# flap.net
KiCad netlist of a schematic drawn in Altium Designer
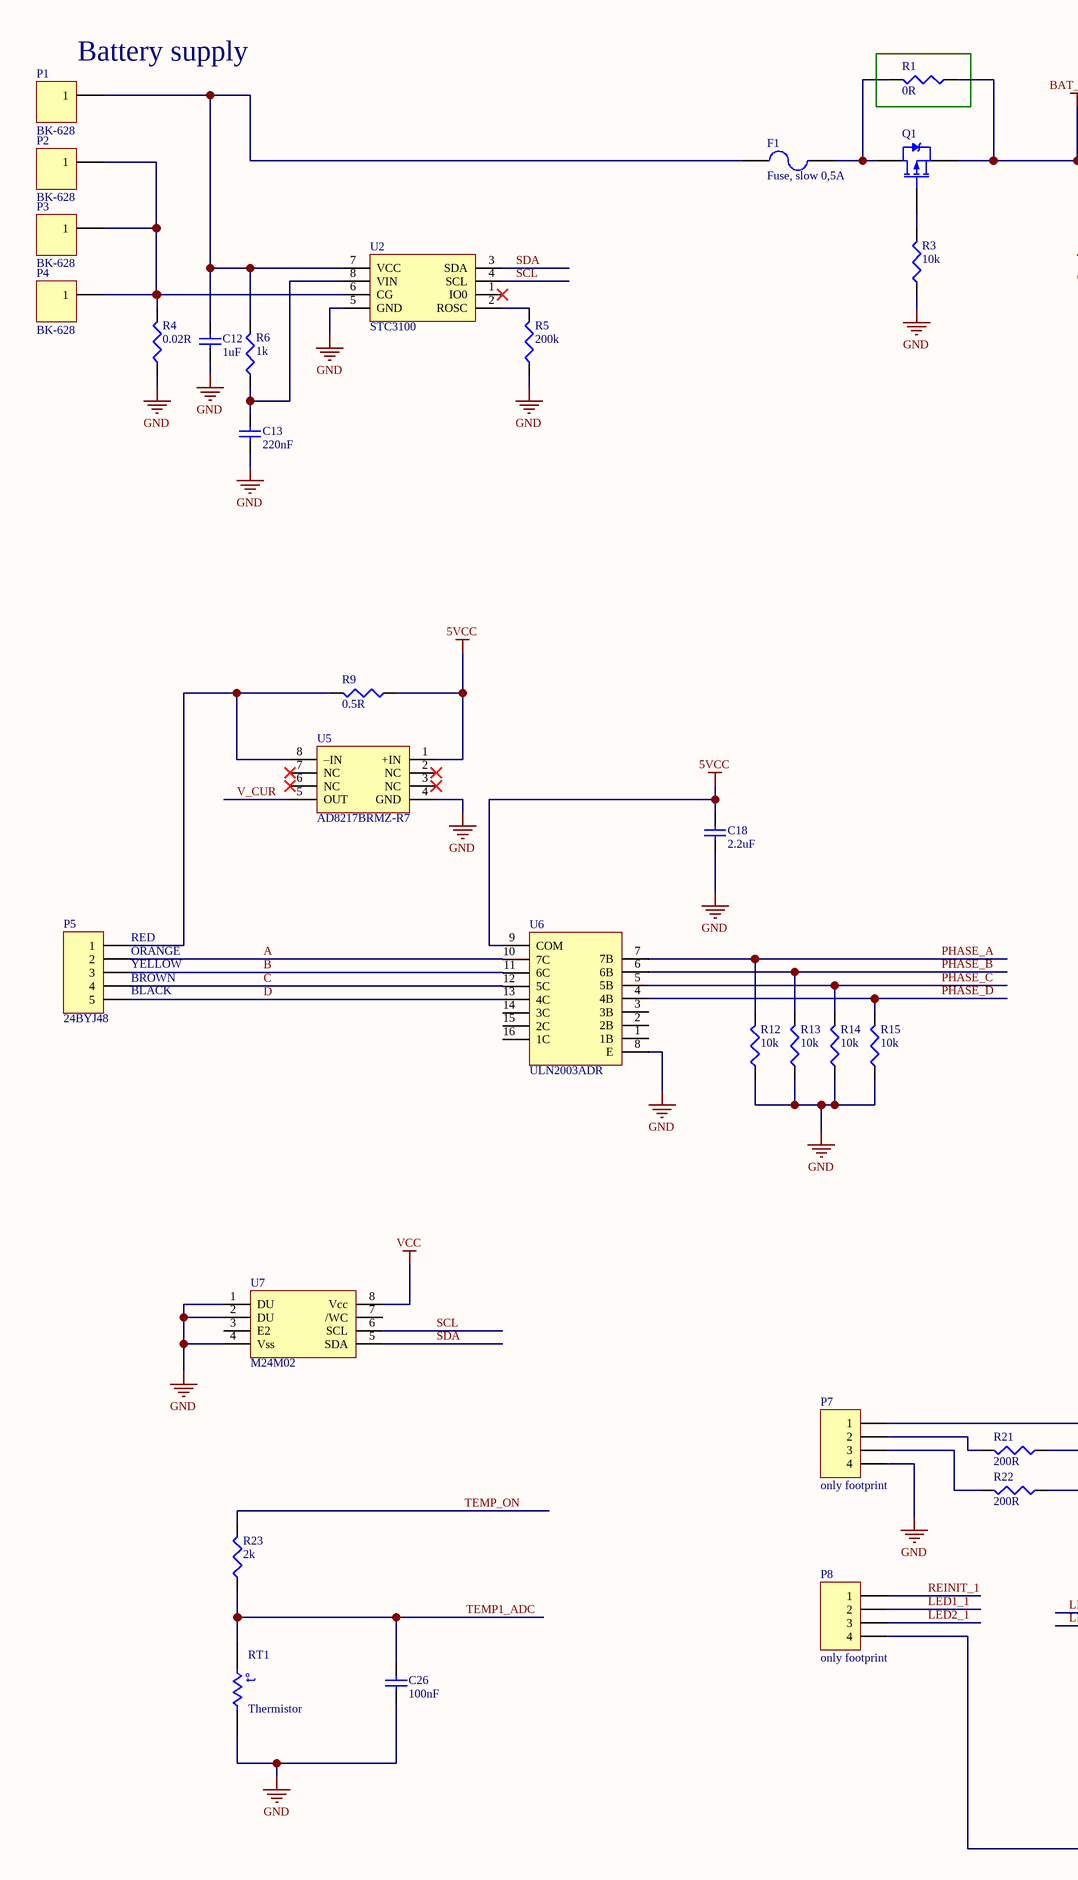
[diagram p0: flap.SchDoc, left]
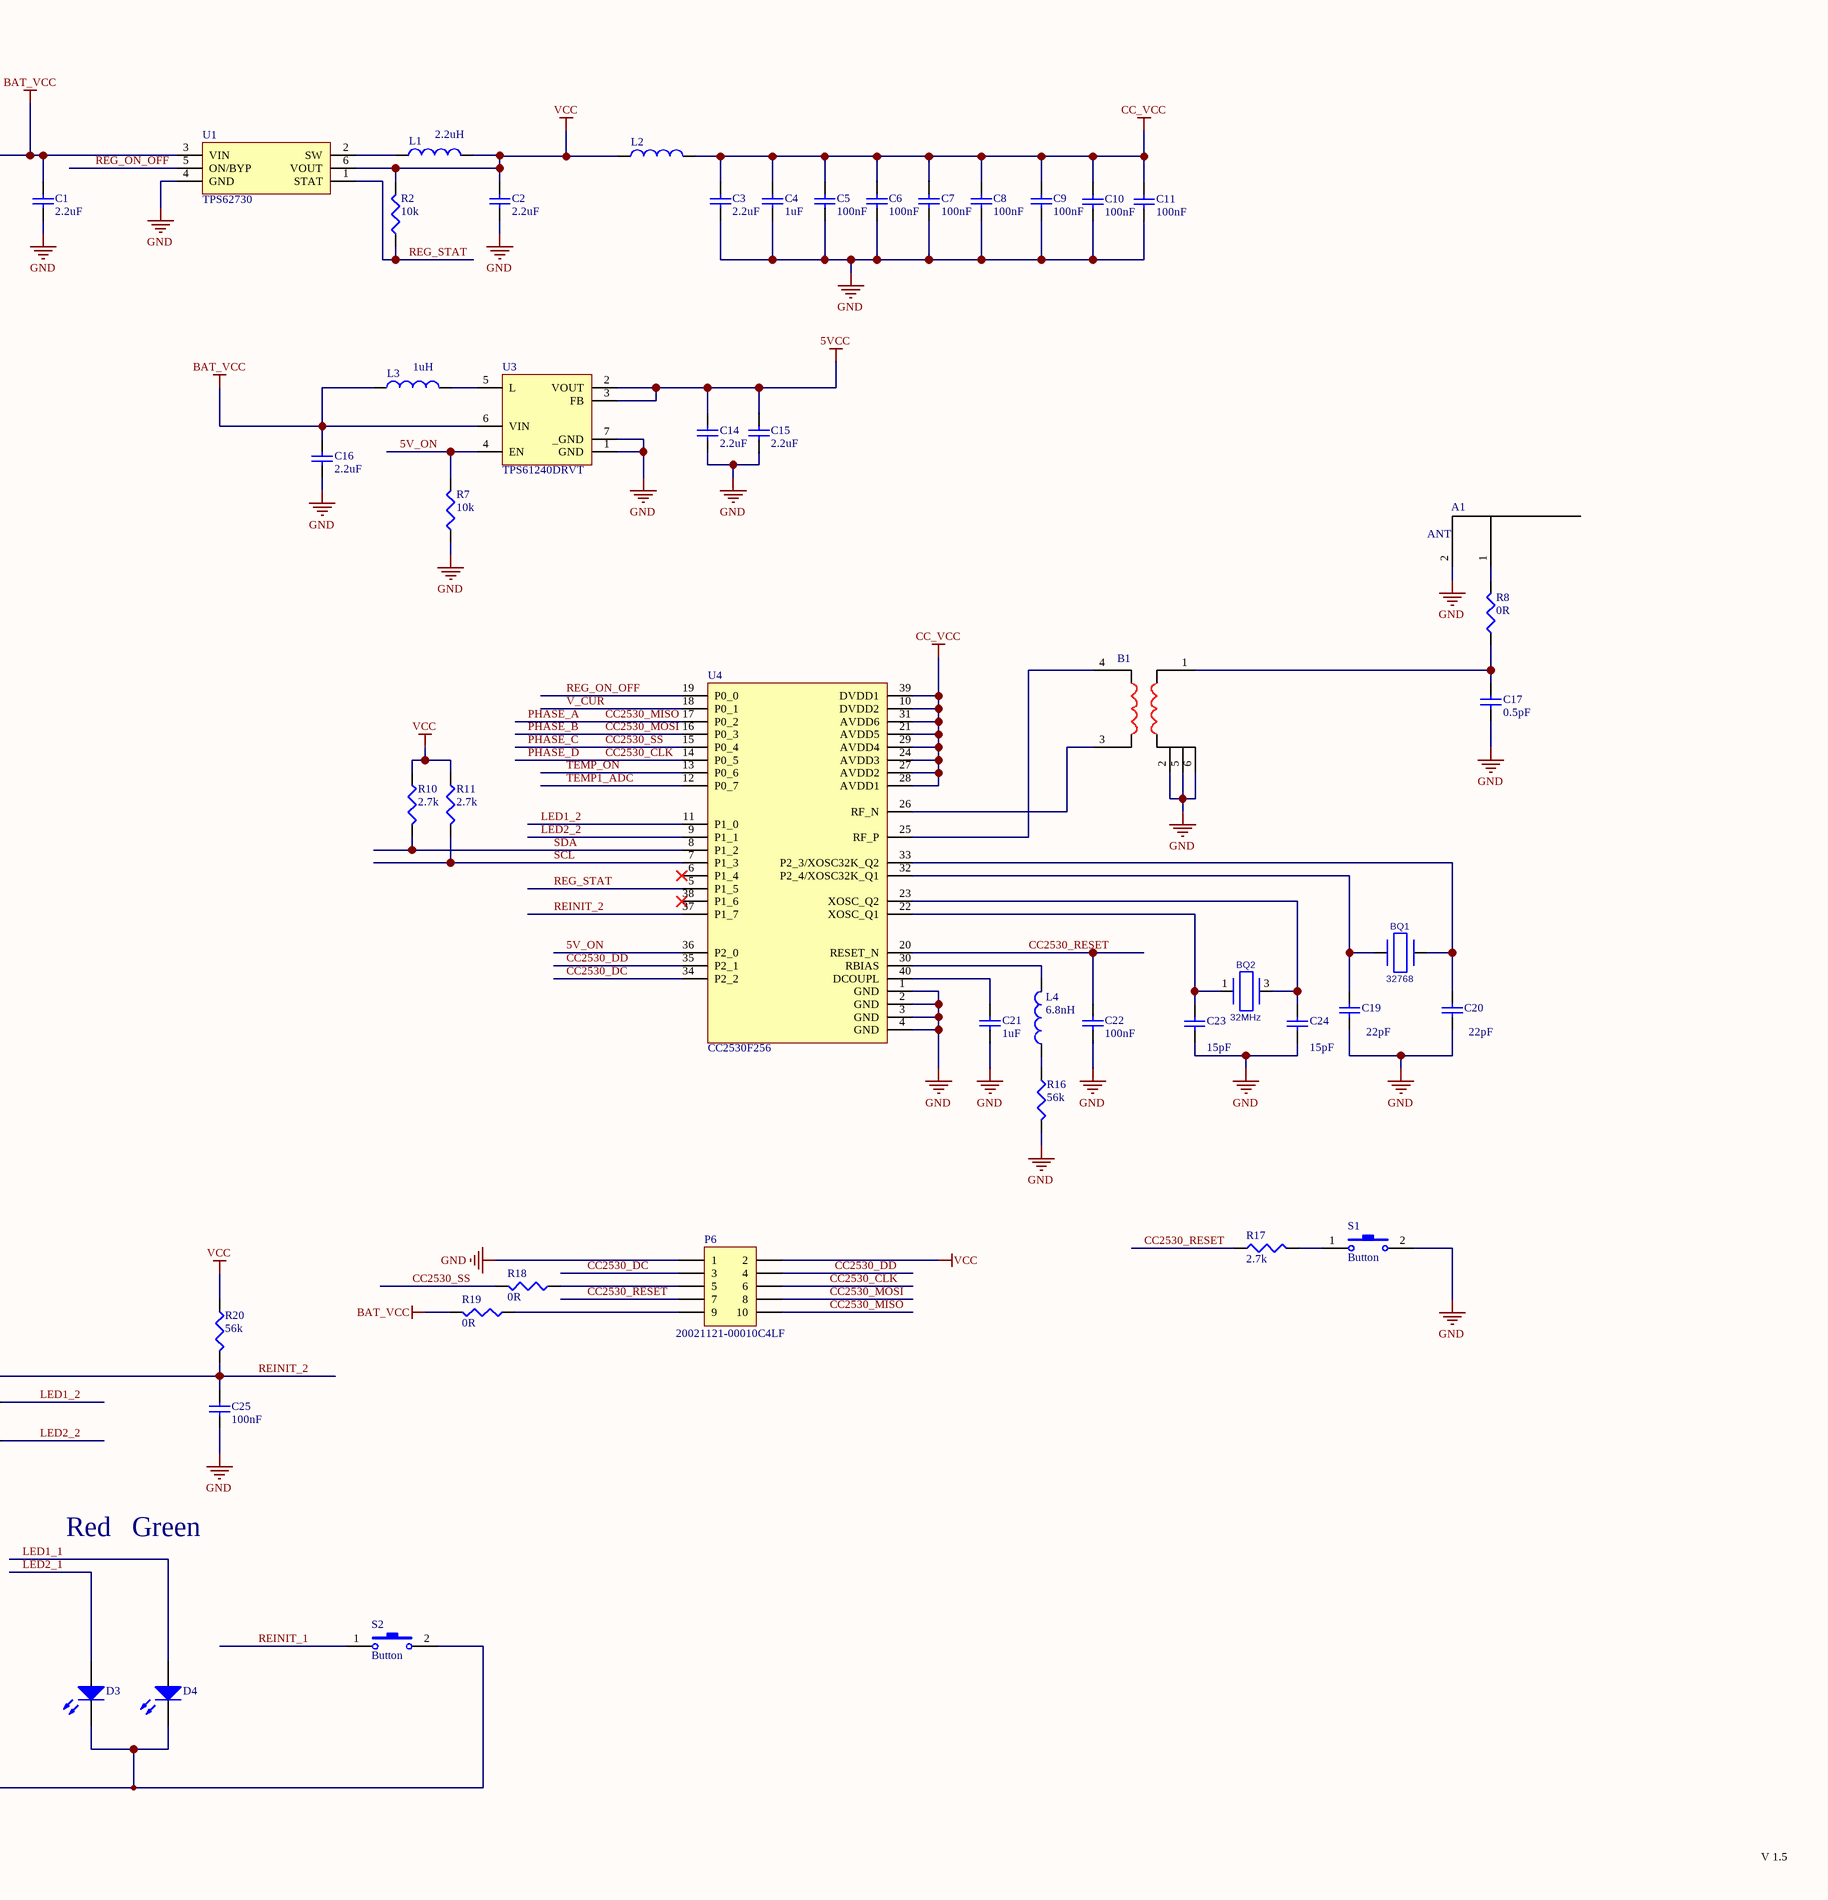
[diagram p1: flap.SchDoc, right]

(export (version "E")
  (design (tool "Eeschema 10.0.6"))
  (components
    (comp (ref "A1")
      (value "ANT")
      (footprint "F ant")
      (description "Inverted-F Antenna")
      (fields (field (name "MANUFACTURER PART NUMBER") "PCB ANT"))
      (libsource (lib "CC25xx") (part "ANT"))
    )
    (comp (ref "B1")
      (value "BALUN")
      (footprint "2450BM15A0002")
      (description "BALUN JTI MATCHED ZIGBEE")
      (fields
        (field (name "MANUFACTURER PART NUMBER") "2450BM15A0002E")
        (field (name "MANUFACTURER") "Johanson Technology Inc")
      )
      (libsource (lib "CC25xx") (part "BALUN"))
    )
    (comp (ref "BQ1")
      (value "32768")
      (footprint "FC-12M")
      (description "CRYSTAL 32.768KHZ 12.5PF SMD")
      (fields
        (field (name "MANUFACTURER PART NUMBER") "FC-12M 32.7680KA-A3")
        (field (name "MANUFACTURER") "EPSON")
      )
      (libsource (lib "*") (part "6LC{colon}308C"))
    )
    (comp (ref "BQ2")
      (value "32MHz")
      (footprint "403C11A32M00000")
      (description "CRYSTAL 32MHZ 10PF SMD")
      (fields
        (field (name "MANUFACTURER PART NUMBER") "403C11A32M00000")
        (field (name "MANUFACTURER") "CTS-Frequency Controls")
      )
      (libsource (lib "*") (part "HC-49SMD"))
    )
    (comp (ref "C1")
      (value "2.2uF")
      (footprint "0402")
      (description "CAP CER 2.2UF 6.3V 20% X5R 0402")
      (fields
        (field (name "MANUFACTURER PART NUMBER") "CL05A225MQ5NNNC")
        (field (name "MANUFACTURER") "Samsung Electro-Mechanics America, Inc")
      )
      (libsource (lib "Miscellaneous Devices") (part "Cap"))
    )
    (comp (ref "C2")
      (value "2.2uF")
      (footprint "0402")
      (description "CAP CER 2.2UF 6.3V 20% X5R 0402")
      (fields
        (field (name "MANUFACTURER PART NUMBER") "CL05A225MQ5NNNC")
        (field (name "MANUFACTURER") "Samsung Electro-Mechanics America, Inc")
      )
      (libsource (lib "Miscellaneous Devices") (part "Cap"))
    )
    (comp (ref "C3")
      (value "2.2uF")
      (footprint "0402")
      (description "CAP CER 2.2UF 6.3V 20% X5R 0402")
      (fields
        (field (name "MANUFACTURER PART NUMBER") "CL05A225MQ5NNNC")
        (field (name "MANUFACTURER") "Samsung Electro-Mechanics America, Inc")
      )
      (libsource (lib "Miscellaneous Devices") (part "Cap"))
    )
    (comp (ref "C4")
      (value "1uF")
      (footprint "0402")
      (description "CAP CER 1UF 6.3V 10% X5R 0402")
      (fields
        (field (name "MANUFACTURER PART NUMBER") "GRM155R60J105KE19D")
        (field (name "MANUFACTURER") "Murata Electronics North America")
      )
      (libsource (lib "Miscellaneous Devices") (part "Cap"))
    )
    (comp (ref "C5")
      (value "100nF")
      (footprint "0402")
      (description "CAP CER 0.1UF 10V 20% X5R 0402")
      (fields
        (field (name "MANUFACTURER PART NUMBER") "CL05A104MP5NNNC")
        (field (name "MANUFACTURER") "Samsung Electro-Mechanics America, Inc")
      )
      (libsource (lib "Miscellaneous Devices") (part "Cap"))
    )
    (comp (ref "C6")
      (value "100nF")
      (footprint "0402")
      (description "CAP CER 0.1UF 10V 20% X5R 0402")
      (fields
        (field (name "MANUFACTURER PART NUMBER") "CL05A104MP5NNNC")
        (field (name "MANUFACTURER") "Samsung Electro-Mechanics America, Inc")
      )
      (libsource (lib "Miscellaneous Devices") (part "Cap"))
    )
    (comp (ref "C7")
      (value "100nF")
      (footprint "0402")
      (description "CAP CER 0.1UF 10V 20% X5R 0402")
      (fields
        (field (name "MANUFACTURER PART NUMBER") "CL05A104MP5NNNC")
        (field (name "MANUFACTURER") "Samsung Electro-Mechanics America, Inc")
      )
      (libsource (lib "Miscellaneous Devices") (part "Cap"))
    )
    (comp (ref "C8")
      (value "100nF")
      (footprint "0402")
      (description "CAP CER 0.1UF 10V 20% X5R 0402")
      (fields
        (field (name "MANUFACTURER PART NUMBER") "CL05A104MP5NNNC")
        (field (name "MANUFACTURER") "Samsung Electro-Mechanics America, Inc")
      )
      (libsource (lib "Miscellaneous Devices") (part "Cap"))
    )
    (comp (ref "C9")
      (value "100nF")
      (footprint "0402")
      (description "CAP CER 0.1UF 10V 20% X5R 0402")
      (fields
        (field (name "MANUFACTURER PART NUMBER") "CL05A104MP5NNNC")
        (field (name "MANUFACTURER") "Samsung Electro-Mechanics America, Inc")
      )
      (libsource (lib "Miscellaneous Devices") (part "Cap"))
    )
    (comp (ref "C10")
      (value "100nF")
      (footprint "0402")
      (description "CAP CER 0.1UF 10V 20% X5R 0402")
      (fields
        (field (name "MANUFACTURER PART NUMBER") "CL05A104MP5NNNC")
        (field (name "MANUFACTURER") "Samsung Electro-Mechanics America, Inc")
      )
      (libsource (lib "Miscellaneous Devices") (part "Cap"))
    )
    (comp (ref "C11")
      (value "100nF")
      (footprint "0402")
      (description "CAP CER 0.1UF 10V 20% X5R 0402")
      (fields
        (field (name "MANUFACTURER PART NUMBER") "CL05A104MP5NNNC")
        (field (name "MANUFACTURER") "Samsung Electro-Mechanics America, Inc")
      )
      (libsource (lib "Miscellaneous Devices") (part "Cap"))
    )
    (comp (ref "C12")
      (value "1uF")
      (footprint "0402")
      (description "CAP CER 1UF 6.3V 10% X5R 0402")
      (fields
        (field (name "MANUFACTURER PART NUMBER") "GRM155R60J105KE19D")
        (field (name "MANUFACTURER") "Murata Electronics North America")
      )
      (libsource (lib "Miscellaneous Devices") (part "Cap"))
    )
    (comp (ref "C13")
      (value "220nF")
      (footprint "0402")
      (description "CAP CER 0.22UF 10V 10% X5R 0402")
      (fields
        (field (name "MANUFACTURER PART NUMBER") "CL05A224KP5NNNC")
        (field (name "MANUFACTURER") "Samsung Electro-Mechanics America, Inc")
      )
      (libsource (lib "Miscellaneous Devices") (part "Cap"))
    )
    (comp (ref "C14")
      (value "2.2uF")
      (footprint "0402")
      (description "CAP CER 2.2UF 6.3V 20% X5R 0402")
      (fields
        (field (name "MANUFACTURER PART NUMBER") "CL05A225MQ5NNNC")
        (field (name "MANUFACTURER") "Samsung Electro-Mechanics America, Inc")
      )
      (libsource (lib "Miscellaneous Devices") (part "Cap"))
    )
    (comp (ref "C15")
      (value "2.2uF")
      (footprint "0402")
      (description "CAP CER 2.2UF 6.3V 20% X5R 0402")
      (fields
        (field (name "MANUFACTURER PART NUMBER") "CL05A225MQ5NNNC")
        (field (name "MANUFACTURER") "Samsung Electro-Mechanics America, Inc")
      )
      (libsource (lib "Miscellaneous Devices") (part "Cap"))
    )
    (comp (ref "C16")
      (value "2.2uF")
      (footprint "0402")
      (description "CAP CER 2.2UF 6.3V 20% X5R 0402")
      (fields
        (field (name "MANUFACTURER PART NUMBER") "CL05A225MQ5NNNC")
        (field (name "MANUFACTURER") "Samsung Electro-Mechanics America, Inc")
      )
      (libsource (lib "Miscellaneous Devices") (part "Cap"))
    )
    (comp (ref "C17")
      (value "0.5pF")
      (footprint "0402")
      (description "CAP CER 0.5PF 50V NP0 0402")
      (fields
        (field (name "MANUFACTURER PART NUMBER") "GRM1555C1HR50CA01D")
        (field (name "MANUFACTURER") "Murata Electronics North America")
      )
      (libsource (lib "Miscellaneous Devices") (part "Cap"))
    )
    (comp (ref "C18")
      (value "2.2uF")
      (footprint "0402")
      (description "CAP CER 2.2UF 6.3V 20% X5R 0402")
      (fields
        (field (name "MANUFACTURER PART NUMBER") "CL05A225MQ5NNNC")
        (field (name "MANUFACTURER") "Samsung Electro-Mechanics America, Inc")
      )
      (libsource (lib "Miscellaneous Devices") (part "Cap"))
    )
    (comp (ref "C19")
      (value "22pF")
      (footprint "0402")
      (description "CAP CER 22PF 50V 5% NP0 0402")
      (fields
        (field (name "MANUFACTURER PART NUMBER") "GRM1555C1H220JA01D")
        (field (name "MANUFACTURER") "Murata Electronics North America")
      )
      (libsource (lib "Miscellaneous Devices") (part "Cap"))
    )
    (comp (ref "C20")
      (value "22pF")
      (footprint "0402")
      (description "CAP CER 22PF 50V 5% NP0 0402")
      (fields
        (field (name "MANUFACTURER PART NUMBER") "GRM1555C1H220JA01D")
        (field (name "MANUFACTURER") "Murata Electronics North America")
      )
      (libsource (lib "Miscellaneous Devices") (part "Cap"))
    )
    (comp (ref "C21")
      (value "1uF")
      (footprint "0402")
      (description "CAP CER 1UF 6.3V 10% X5R 0402")
      (fields
        (field (name "MANUFACTURER PART NUMBER") "GRM155R60J105KE19D")
        (field (name "MANUFACTURER") "Murata Electronics North America")
      )
      (libsource (lib "Miscellaneous Devices") (part "Cap"))
    )
    (comp (ref "C22")
      (value "100nF")
      (footprint "0402")
      (description "CAP CER 0.1UF 10V 20% X5R 0402")
      (fields
        (field (name "MANUFACTURER PART NUMBER") "CL05A104MP5NNNC")
        (field (name "MANUFACTURER") "Samsung Electro-Mechanics America, Inc")
      )
      (libsource (lib "Miscellaneous Devices") (part "Cap"))
    )
    (comp (ref "C23")
      (value "15pF")
      (footprint "0402")
      (description "CAP CER 15PF 50V 5% NP0 0402")
      (fields
        (field (name "MANUFACTURER PART NUMBER") "GRM1555C1H150JA01D")
        (field (name "MANUFACTURER") "Murata Electronics North America")
      )
      (libsource (lib "Miscellaneous Devices") (part "Cap"))
    )
    (comp (ref "C24")
      (value "15pF")
      (footprint "0402")
      (description "CAP CER 15PF 50V 5% NP0 0402")
      (fields
        (field (name "MANUFACTURER PART NUMBER") "GRM1555C1H150JA01D")
        (field (name "MANUFACTURER") "Murata Electronics North America")
      )
      (libsource (lib "Miscellaneous Devices") (part "Cap"))
    )
    (comp (ref "C25")
      (value "100nF")
      (footprint "0402")
      (description "CAP CER 0.1UF 10V 20% X5R 0402")
      (fields
        (field (name "MANUFACTURER PART NUMBER") "CL05A104MP5NNNC")
        (field (name "MANUFACTURER") "Samsung Electro-Mechanics America, Inc")
      )
      (libsource (lib "Miscellaneous Devices") (part "Cap"))
    )
    (comp (ref "C26")
      (value "100nF")
      (footprint "0402")
      (description "CAP CER 0.1UF 10V 20% X5R 0402")
      (fields
        (field (name "MANUFACTURER PART NUMBER") "CL05A104MP5NNNC")
        (field (name "MANUFACTURER") "Samsung Electro-Mechanics America, Inc")
      )
      (libsource (lib "Miscellaneous Devices") (part "Cap"))
    )
    (comp (ref "D3")
      (value "Led")
      (footprint "LED0603")
      (description "LED SUPER RED CLEAR 0603 SMD")
      (fields
        (field (name "MANUFACTURER PART NUMBER") "LTST-C190KRKT")
        (field (name "MANUFACTURER") "Lite-On Inc")
      )
      (libsource (lib "Miscellaneous Devices") (part "LED0"))
    )
    (comp (ref "D4")
      (value "Led")
      (footprint "LED0603")
      (description "LED GREEN CLEAR THIN 0603 SMD")
      (fields
        (field (name "MANUFACTURER PART NUMBER") "LTST-C191KGKT")
        (field (name "MANUFACTURER") "Lite-On Inc")
      )
      (libsource (lib "Miscellaneous Devices") (part "LED0"))
    )
    (comp (ref "F1")
      (value "Fuse, slow 0,5A")
      (footprint "SF1206S0502")
      (description "FUSE 0,5A 63V 1206 SLOW")
      (fields
        (field (name "MANUFACTURER PART NUMBER") "SF-1206S050-2")
        (field (name "MANUFACTURER") "Bourns Inc.")
      )
      (libsource (lib "Miscellaneous Devices") (part "Fuse 2"))
    )
    (comp (ref "L1")
      (value "2.2uH")
      (footprint "6-0805_L")
      (description "INDUCTOR 2.2UH 0805")
      (fields
        (field (name "MANUFACTURER PART NUMBER") "LQM21PN2R2NGCD")
        (field (name "MANUFACTURER") "Murata Electronics North America")
      )
      (libsource (lib "Miscellaneous Devices") (part "Inductor"))
    )
    (comp (ref "L2")
      (value "Inductor")
      (footprint "0402")
      (description "FILTER CHIP 1000 OHM 250MA 0402")
      (fields
        (field (name "MANUFACTURER PART NUMBER") "BLM15HG102SN1D")
        (field (name "MANUFACTURER") "Murata Electronics North America")
      )
      (libsource (lib "Miscellaneous Devices") (part "Inductor"))
    )
    (comp (ref "L3")
      (value "1uH")
      (footprint "1008")
      (description "INDUCTOR POWER 1UH 2.2A 1008")
      (fields
        (field (name "MANUFACTURER PART NUMBER") "CIG22E1R0MNE")
        (field (name "MANUFACTURER") "Samsung Electro-Mechanics America, Inc")
      )
      (libsource (lib "Miscellaneous Devices") (part "Inductor"))
    )
    (comp (ref "L4")
      (value "6.8nH")
      (footprint "0402")
      (description "INDUCTOR 6.8NH 300MA 0402")
      (fields
        (field (name "MANUFACTURER PART NUMBER") "LQG15HS6N8J02D")
        (field (name "MANUFACTURER") "Murata Electronics North America")
      )
      (libsource (lib "Miscellaneous Devices") (part "Inductor"))
    )
    (comp (ref "P1")
      (value "Connector")
      (footprint "BAT_CLIP1")
      (description "CONTACT BATTERY AA NEGATIVE")
      (fields
        (field (name "MANUFACTURER PART NUMBER") "BK-628")
        (field (name "MANUFACTURER") "MPD (Memory Protection Devices)")
      )
      (libsource (lib "Miscellaneous Connectors") (part "Header 2"))
    )
    (comp (ref "P2")
      (value "Connector")
      (footprint "BAT_CLIP1")
      (description "CONTACT BATTERY AA NEGATIVE")
      (fields
        (field (name "MANUFACTURER PART NUMBER") "BK-628")
        (field (name "MANUFACTURER") "MPD (Memory Protection Devices)")
      )
      (libsource (lib "Miscellaneous Connectors") (part "Header 2"))
    )
    (comp (ref "P3")
      (value "Connector")
      (footprint "BAT_CLIP1")
      (description "CONTACT BATTERY AA NEGATIVE")
      (fields
        (field (name "MANUFACTURER PART NUMBER") "BK-628")
        (field (name "MANUFACTURER") "MPD (Memory Protection Devices)")
      )
      (libsource (lib "Miscellaneous Connectors") (part "Header 2"))
    )
    (comp (ref "P4")
      (value "Connector")
      (footprint "BAT_CLIP1")
      (description "CONTACT BATTERY AA NEGATIVE")
      (fields
        (field (name "MANUFACTURER PART NUMBER") "BK-628")
        (field (name "MANUFACTURER") "MPD (Memory Protection Devices)")
      )
      (libsource (lib "Miscellaneous Connectors") (part "Header 2"))
    )
    (comp (ref "P5")
      (value "24BYJ48")
      (footprint "HDR1X5H")
      (description "Header, 5-Pin, Right Angle")
      (fields (field (name "MANUFACTURER PART NUMBER") "68016-205HLF") (field (name "MANUFACTURER") "FCI"))
      (libsource (lib "Miscellaneous Connectors") (part "Header 5H"))
    )
    (comp (ref "P6")
      (value "*")
      (footprint "20021121-00010C4LF")
      (description "CONN HEADER 10POS DL UNSHRD SMD")
      (fields
        (field (name "MANUFACTURER PART NUMBER") "20021121-00010C4LF")
        (field (name "MANUFACTURER") "FCI")
      )
      (libsource (lib "Miscellaneous Connectors") (part "Header 5X2"))
    )
    (comp (ref "P7")
      (value "Header 4")
      (footprint "HDR1X4")
      (description "Header, 4-Pin")
      (fields (field (name "MANUFACTURER PART NUMBER") "only footprint"))
      (libsource (lib "Miscellaneous Connectors") (part "Header 4"))
    )
    (comp (ref "P8")
      (value "Header 4")
      (footprint "HDR1X4")
      (description "Header, 4-Pin")
      (fields (field (name "MANUFACTURER PART NUMBER") "only footprint"))
      (libsource (lib "Miscellaneous Connectors") (part "Header 4"))
    )
    (comp (ref "Q1")
      (value "IRLML6302GTRPBF")
      (footprint "SOT-23_N")
      (description "HEXFET Power MOSFET")
      (fields
        (field (name "MANUFACTURER") "International Rectifier")
        (field (name "PUBLISHER") "Altium Limited")
      )
      (libsource (lib "IR Discrete MOSFET - Power") (part "IRLML6302"))
    )
    (comp (ref "R1")
      (value "0R")
      (footprint "0402")
      (description "RES 0.0 OHM 1/10W JUMP 0402 SMD")
      (fields
        (field (name "MANUFACTURER PART NUMBER") "ERJ-2GE0R00X")
        (field (name "MANUFACTURER") "Panasonic Electronic Components")
      )
      (libsource (lib "Miscellaneous Devices") (part "Res3"))
    )
    (comp (ref "R2")
      (value "10k")
      (footprint "0402")
      (description "RES 10K OHM 1/10W 5% 0402 SMD")
      (fields
        (field (name "MANUFACTURER PART NUMBER") "ERJ-2GEJ103X")
        (field (name "MANUFACTURER") "Panasonic Electronic Components")
      )
      (libsource (lib "Miscellaneous Devices") (part "Res3"))
    )
    (comp (ref "R3")
      (value "10k")
      (footprint "0402")
      (description "RES 10K OHM 1/10W 5% 0402 SMD")
      (fields
        (field (name "MANUFACTURER PART NUMBER") "ERJ-2GEJ103X")
        (field (name "MANUFACTURER") "Panasonic Electronic Components")
      )
      (libsource (lib "Miscellaneous Devices") (part "Res3"))
    )
    (comp (ref "R4")
      (value "0.02R")
      (footprint "0603")
      (description "RES 0.02 OHM 1/4W 1% 0603")
      (fields
        (field (name "MANUFACTURER PART NUMBER") "RU1608FR020CS")
        (field (name "MANUFACTURER") "Samsung Electro-Mechanics America, Inc")
      )
      (libsource (lib "Miscellaneous Devices") (part "Res3"))
    )
    (comp (ref "R5")
      (value "200k")
      (footprint "6-0805_L")
      (description "RES 200K OHM 1/8W .1% 0805 SMD")
      (fields
        (field (name "MANUFACTURER PART NUMBER") "ERA-6AEB204V")
        (field (name "MANUFACTURER") "Panasonic Electronic Components")
      )
      (libsource (lib "Miscellaneous Devices") (part "Res3"))
    )
    (comp (ref "R6")
      (value "1k")
      (footprint "0402")
      (description "RES 1K OHM 1/10W 1% 0402 SMD")
      (fields
        (field (name "MANUFACTURER PART NUMBER") "ERJ-2RKF1001X")
        (field (name "MANUFACTURER") "Panasonic Electronic Components")
      )
      (libsource (lib "Miscellaneous Devices") (part "Res3"))
    )
    (comp (ref "R7")
      (value "10k")
      (footprint "0402")
      (description "RES 10K OHM 1/10W 5% 0402 SMD")
      (fields
        (field (name "MANUFACTURER PART NUMBER") "ERJ-2GEJ103X")
        (field (name "MANUFACTURER") "Panasonic Electronic Components")
      )
      (libsource (lib "Miscellaneous Devices") (part "Res3"))
    )
    (comp (ref "R8")
      (value "0R")
      (footprint "0402")
      (description "RES 0.0 OHM 1/10W JUMP 0402 SMD")
      (fields
        (field (name "MANUFACTURER PART NUMBER") "ERJ-2GE0R00X")
        (field (name "MANUFACTURER") "Panasonic Electronic Components")
      )
      (libsource (lib "Miscellaneous Devices") (part "Res3"))
    )
    (comp (ref "R9")
      (value "0.5R")
      (footprint "0402")
      (description "RES 0.5 OHM 1/16W 1% 0402 SMD")
      (fields
        (field (name "MANUFACTURER PART NUMBER") "RL0402FR-070R5L")
        (field (name "MANUFACTURER") "Yageo")
      )
      (libsource (lib "Miscellaneous Devices") (part "Res3"))
    )
    (comp (ref "R10")
      (value "2.7k")
      (footprint "0402")
      (description "RES 2.7K OHM 1/10W 5% 0402 SMD")
      (fields
        (field (name "MANUFACTURER PART NUMBER") "ERJ-2GEJ272X")
        (field (name "MANUFACTURER") "Panasonic Electronic Components")
      )
      (libsource (lib "Miscellaneous Devices") (part "Res3"))
    )
    (comp (ref "R11")
      (value "2.7k")
      (footprint "0402")
      (description "RES 2.7K OHM 1/10W 5% 0402 SMD")
      (fields
        (field (name "MANUFACTURER PART NUMBER") "ERJ-2GEJ272X")
        (field (name "MANUFACTURER") "Panasonic Electronic Components")
      )
      (libsource (lib "Miscellaneous Devices") (part "Res3"))
    )
    (comp (ref "R12")
      (value "10k")
      (footprint "0402")
      (description "RES 10K OHM 1/10W 5% 0402 SMD")
      (fields
        (field (name "MANUFACTURER PART NUMBER") "ERJ-2GEJ103X")
        (field (name "MANUFACTURER") "Panasonic Electronic Components")
      )
      (libsource (lib "Miscellaneous Devices") (part "Res3"))
    )
    (comp (ref "R13")
      (value "10k")
      (footprint "0402")
      (description "RES 10K OHM 1/10W 5% 0402 SMD")
      (fields
        (field (name "MANUFACTURER PART NUMBER") "ERJ-2GEJ103X")
        (field (name "MANUFACTURER") "Panasonic Electronic Components")
      )
      (libsource (lib "Miscellaneous Devices") (part "Res3"))
    )
    (comp (ref "R14")
      (value "10k")
      (footprint "0402")
      (description "RES 10K OHM 1/10W 5% 0402 SMD")
      (fields
        (field (name "MANUFACTURER PART NUMBER") "ERJ-2GEJ103X")
        (field (name "MANUFACTURER") "Panasonic Electronic Components")
      )
      (libsource (lib "Miscellaneous Devices") (part "Res3"))
    )
    (comp (ref "R15")
      (value "10k")
      (footprint "0402")
      (description "RES 10K OHM 1/10W 5% 0402 SMD")
      (fields
        (field (name "MANUFACTURER PART NUMBER") "ERJ-2GEJ103X")
        (field (name "MANUFACTURER") "Panasonic Electronic Components")
      )
      (libsource (lib "Miscellaneous Devices") (part "Res3"))
    )
    (comp (ref "R16")
      (value "56k")
      (footprint "0402")
      (description "RES 56K OHM 1/10W 1% 0402 SMD")
      (fields
        (field (name "MANUFACTURER PART NUMBER") "ERJ-2RKF5602X")
        (field (name "MANUFACTURER") "Panasonic Electronic Components")
      )
      (libsource (lib "Miscellaneous Devices") (part "Res3"))
    )
    (comp (ref "R17")
      (value "2.7k")
      (footprint "0402")
      (description "RES 2.7K OHM 1/10W 5% 0402 SMD")
      (fields
        (field (name "MANUFACTURER PART NUMBER") "ERJ-2GEJ272X")
        (field (name "MANUFACTURER") "Panasonic Electronic Components")
      )
      (libsource (lib "Miscellaneous Devices") (part "Res3"))
    )
    (comp (ref "R18")
      (value "0R")
      (footprint "0402")
      (description "RES 0.0 OHM 1/10W JUMP 0402 SMD")
      (fields
        (field (name "MANUFACTURER PART NUMBER") "ERJ-2GE0R00X")
        (field (name "MANUFACTURER") "Panasonic Electronic Components")
      )
      (libsource (lib "Miscellaneous Devices") (part "Res3"))
    )
    (comp (ref "R19")
      (value "0R")
      (footprint "0402")
      (description "RES 0.0 OHM 1/10W JUMP 0402 SMD")
      (fields
        (field (name "MANUFACTURER PART NUMBER") "ERJ-2GE0R00X")
        (field (name "MANUFACTURER") "Panasonic Electronic Components")
      )
      (libsource (lib "Miscellaneous Devices") (part "Res3"))
    )
    (comp (ref "R20")
      (value "56k")
      (footprint "0402")
      (description "RES 56K OHM 1/10W 1% 0402 SMD")
      (fields
        (field (name "MANUFACTURER PART NUMBER") "ERJ-2RKF5602X")
        (field (name "MANUFACTURER") "Panasonic Electronic Components")
      )
      (libsource (lib "Miscellaneous Devices") (part "Res3"))
    )
    (comp (ref "R21")
      (value "200R")
      (footprint "0603")
      (description "RES 200 OHM 1/10W 5% 0603 SMD")
      (fields
        (field (name "MANUFACTURER PART NUMBER") "RC0603JR-07200RL")
        (field (name "MANUFACTURER") "Yageo")
      )
      (libsource (lib "Miscellaneous Devices") (part "Res3"))
    )
    (comp (ref "R22")
      (value "200R")
      (footprint "0603")
      (description "RES 200 OHM 1/10W 5% 0603 SMD")
      (fields
        (field (name "MANUFACTURER PART NUMBER") "RC0603JR-07200RL")
        (field (name "MANUFACTURER") "Yageo")
      )
      (libsource (lib "Miscellaneous Devices") (part "Res3"))
    )
    (comp (ref "R23")
      (value "2k")
      (footprint "0603")
      (description "RES 2.0K OHM 1/10W 5% 0603 SMD")
      (fields
        (field (name "MANUFACTURER PART NUMBER") "RC0603JR-072KL")
        (field (name "MANUFACTURER") "Yageo")
      )
      (libsource (lib "Miscellaneous Devices") (part "Res3"))
    )
    (comp (ref "RT1")
      (value "Thermistor")
      (footprint "0603")
      (description "THERMISTOR NTC 1K OHM 5% 0603")
      (fields
        (field (name "MANUFACTURER PART NUMBER") "ERT-J1VT102J")
        (field (name "MANUFACTURER") "Panasonic Electronic Components")
      )
      (libsource (lib "Miscellaneous Devices") (part "Res Thermal"))
    )
    (comp (ref "S1")
      (value "Button")
      (footprint "EVQP2402W")
      (description "SWITCH TACTILE SPST-NO 0.02A 15V")
      (fields
        (field (name "MANUFACTURER PART NUMBER") "EVQ-P2402W")
        (field (name "MANUFACTURER") "Panasonic Electronic Components")
      )
      (libsource (lib "Miscellaneous Devices") (part "SW-PB"))
    )
    (comp (ref "S2")
      (value "Button")
      (footprint "EVQP2402W")
      (description "SWITCH TACTILE SPST-NO 0.02A 15V")
      (fields
        (field (name "MANUFACTURER PART NUMBER") "EVQ-P2402W")
        (field (name "MANUFACTURER") "Panasonic Electronic Components")
      )
      (libsource (lib "Miscellaneous Devices") (part "SW-PB"))
    )
    (comp (ref "U1")
      (value "TPS62730")
      (footprint "6SON")
      (description "IC DCDC CONV STP-DN SYNC LP 6SON")
      (fields
        (field (name "MANUFACTURER PART NUMBER") "TPS62730DRYT")
        (field (name "MANUFACTURER") "Texas Instruments")
      )
      (libsource (lib "thermostat_main") (part "TPS62730"))
    )
    (comp (ref "U2")
      (value "STC3100")
      (footprint "DFN8")
      (description "IC BATTERY MON W/GAUGE 8-DFN")
      (fields
        (field (name "MANUFACTURER PART NUMBER") "STC3100IQT")
        (field (name "MANUFACTURER") "STMicroelectronics")
      )
      (libsource (lib "CC25xx") (part "STC3100"))
    )
    (comp (ref "U3")
      (value "TPS61240DRVT")
      (footprint "WSON6")
      (description "IC REG BOOST SYNC 5V 0.45A 6SON")
      (fields (field (name "MANUFACTURER") "Texas Instruments"))
      (libsource (lib "CC25xx") (part "TPS61240DRVT"))
    )
    (comp (ref "U4")
      (value "CC2530F256")
      (footprint "QFN40")
      (description "IC SOC IEEE 802.15.4/ZIG 40VQFN")
      (fields
        (field (name "MANUFACTURER PART NUMBER") "CC2530F256RHAT")
        (field (name "MANUFACTURER") "Texas Instruments")
      )
      (libsource (lib "CC25xx") (part "CC2530F256"))
    )
    (comp (ref "U5")
      (value "AD8217BRMZ-R7")
      (footprint "8MSOP")
      (description "IC CURRENT MONITOR HI SIDE 8MSOP")
      (fields (field (name "MANUFACTURER") "Analog Devices Inc"))
      (libsource (lib "CC25xx") (part "AD8217BRMZ-R7"))
    )
    (comp (ref "U6")
      (value "ULN2003ADR")
      (footprint "16SOIC")
      (description "TRANS 7 NPN DARL 50V 500MA 16SO")
      (fields (field (name "MANUFACTURER") "Texas Instruments"))
      (libsource (lib "CC25xx") (part "ULN2004ADR"))
    )
    (comp (ref "U7")
      (value "M24M02")
      (footprint "SO8")
      (description "IC EEPROM 2MBIT 1MHZ 8SO")
      (fields
        (field (name "MANUFACTURER PART NUMBER") "M24M02-DRMN6TP")
        (field (name "MANUFACTURER") "STMicroelectronics")
      )
      (libsource (lib "CC25xx") (part "M24M02"))
    )
  )
  (nets
    (net (code "1") (name "/5V_ON") (class "Default")
      (node (ref "R7") (pin "1") (pinfunction "1_1") (pintype "passive"))
      (node (ref "U3") (pin "4") (pinfunction "EN_4") (pintype "passive"))
      (node (ref "U4") (pin "36") (pinfunction "P2_0_36") (pintype "passive"))
    )
    (net (code "2") (name "/A") (class "Default")
      (node (ref "P5") (pin "2") (pinfunction "2_2") (pintype "passive"))
      (node (ref "U6") (pin "10") (pinfunction "7C_10") (pintype "passive"))
    )
    (net (code "3") (name "/B") (class "Default")
      (node (ref "P5") (pin "3") (pinfunction "3_3") (pintype "passive"))
      (node (ref "U6") (pin "11") (pinfunction "6C_11") (pintype "passive"))
    )
    (net (code "4") (name "/C") (class "Default")
      (node (ref "P5") (pin "4") (pinfunction "4_4") (pintype "passive"))
      (node (ref "U6") (pin "12") (pinfunction "5C_12") (pintype "passive"))
    )
    (net (code "5") (name "/CC2530_CLK") (class "Default")
      (node (ref "P6") (pin "6") (pinfunction "6_6") (pintype "passive"))
      (node (ref "R15") (pin "1") (pinfunction "1_1") (pintype "passive"))
      (node (ref "U4") (pin "14") (pinfunction "P0_5_14") (pintype "passive"))
      (node (ref "U6") (pin "4") (pinfunction "4B_4") (pintype "passive"))
    )
    (net (code "6") (name "/CC2530_DC") (class "Default")
      (node (ref "P6") (pin "3") (pinfunction "3_3") (pintype "passive"))
      (node (ref "U4") (pin "34") (pinfunction "P2_2_34") (pintype "passive"))
    )
    (net (code "7") (name "/CC2530_DD") (class "Default")
      (node (ref "P6") (pin "4") (pinfunction "4_4") (pintype "passive"))
      (node (ref "U4") (pin "35") (pinfunction "P2_1_35") (pintype "passive"))
    )
    (net (code "8") (name "/CC2530_MISO") (class "Default")
      (node (ref "P6") (pin "10") (pinfunction "10_10") (pintype "passive"))
      (node (ref "R12") (pin "1") (pinfunction "1_1") (pintype "passive"))
      (node (ref "U4") (pin "17") (pinfunction "P0_2_17") (pintype "passive"))
      (node (ref "U6") (pin "7") (pinfunction "7B_7") (pintype "passive"))
    )
    (net (code "9") (name "/CC2530_MOSI") (class "Default")
      (node (ref "P6") (pin "8") (pinfunction "8_8") (pintype "passive"))
      (node (ref "R13") (pin "1") (pinfunction "1_1") (pintype "passive"))
      (node (ref "U4") (pin "16") (pinfunction "P0_3_16") (pintype "passive"))
      (node (ref "U6") (pin "6") (pinfunction "6B_6") (pintype "passive"))
    )
    (net (code "10") (name "/CC2530_RESET") (class "Default")
      (node (ref "C22") (pin "1") (pinfunction "1_1") (pintype "passive"))
      (node (ref "P6") (pin "7") (pinfunction "7_7") (pintype "passive"))
      (node (ref "R17") (pin "2") (pinfunction "2_2") (pintype "passive"))
      (node (ref "U4") (pin "20") (pinfunction "RESET_N_20") (pintype "passive"))
    )
    (net (code "11") (name "/CC2530_SS") (class "Default")
      (node (ref "R14") (pin "1") (pinfunction "1_1") (pintype "passive"))
      (node (ref "R18") (pin "2") (pinfunction "2_2") (pintype "passive"))
      (node (ref "U4") (pin "15") (pinfunction "P0_4_15") (pintype "passive"))
      (node (ref "U6") (pin "5") (pinfunction "5B_5") (pintype "passive"))
    )
    (net (code "12") (name "/D") (class "Default")
      (node (ref "P5") (pin "5") (pinfunction "5_5") (pintype "passive"))
      (node (ref "U6") (pin "13") (pinfunction "4C_13") (pintype "passive"))
    )
    (net (code "13") (name "/LED1_1") (class "Default")
      (node (ref "D4") (pin "1") (pinfunction "A_1") (pintype "passive"))
      (node (ref "P8") (pin "2") (pinfunction "2_2") (pintype "passive"))
    )
    (net (code "14") (name "/LED1_2") (class "Default")
      (node (ref "R21") (pin "2") (pinfunction "2_2") (pintype "passive"))
      (node (ref "U4") (pin "11") (pinfunction "P1_0_11") (pintype "passive"))
    )
    (net (code "15") (name "/LED2_1") (class "Default")
      (node (ref "D3") (pin "1") (pinfunction "A_1") (pintype "passive"))
      (node (ref "P8") (pin "3") (pinfunction "3_3") (pintype "passive"))
    )
    (net (code "16") (name "/LED2_2") (class "Default")
      (node (ref "R22") (pin "2") (pinfunction "2_2") (pintype "passive"))
      (node (ref "U4") (pin "9") (pinfunction "P1_1_9") (pintype "passive"))
    )
    (net (code "17") (name "/REG_ON_OFF") (class "Default")
      (node (ref "U1") (pin "5") (pinfunction "ON/BYP_5") (pintype "passive"))
      (node (ref "U4") (pin "19") (pinfunction "P0_0_19") (pintype "passive"))
    )
    (net (code "18") (name "/REG_STAT") (class "Default")
      (node (ref "R2") (pin "2") (pinfunction "2_2") (pintype "passive"))
      (node (ref "U1") (pin "1") (pinfunction "STAT_1") (pintype "passive"))
      (node (ref "U4") (pin "5") (pinfunction "P1_5_5") (pintype "passive"))
    )
    (net (code "19") (name "/REINIT_1") (class "Default")
      (node (ref "P8") (pin "1") (pinfunction "1_1") (pintype "passive"))
      (node (ref "S2") (pin "1") (pinfunction "1_1") (pintype "passive"))
    )
    (net (code "20") (name "/REINIT_2") (class "Default")
      (node (ref "C25") (pin "1") (pinfunction "1_1") (pintype "passive"))
      (node (ref "P7") (pin "1") (pinfunction "1_1") (pintype "passive"))
      (node (ref "R20") (pin "2") (pinfunction "2_2") (pintype "passive"))
      (node (ref "U4") (pin "37") (pinfunction "P1_7_37") (pintype "passive"))
    )
    (net (code "21") (name "/SCL") (class "Default")
      (node (ref "R11") (pin "1") (pinfunction "1_1") (pintype "passive"))
      (node (ref "U2") (pin "4") (pinfunction "SCL_4") (pintype "passive"))
      (node (ref "U4") (pin "7") (pinfunction "P1_3_7") (pintype "passive"))
      (node (ref "U7") (pin "6") (pinfunction "SCL_6") (pintype "passive"))
    )
    (net (code "22") (name "/SDA") (class "Default")
      (node (ref "R10") (pin "1") (pinfunction "1_1") (pintype "passive"))
      (node (ref "U2") (pin "3") (pinfunction "SDA_3") (pintype "passive"))
      (node (ref "U4") (pin "8") (pinfunction "P1_2_8") (pintype "passive"))
      (node (ref "U7") (pin "5") (pinfunction "SDA_5") (pintype "passive"))
    )
    (net (code "23") (name "/TEMP1_ADC") (class "Default")
      (node (ref "C26") (pin "1") (pinfunction "1_1") (pintype "passive"))
      (node (ref "R23") (pin "1") (pinfunction "1_1") (pintype "passive"))
      (node (ref "RT1") (pin "1") (pinfunction "1_1") (pintype "passive"))
      (node (ref "U4") (pin "12") (pinfunction "P0_7_12") (pintype "passive"))
    )
    (net (code "24") (name "/TEMP_ON") (class "Default")
      (node (ref "R23") (pin "2") (pinfunction "2_2") (pintype "passive"))
      (node (ref "U4") (pin "13") (pinfunction "P0_6_13") (pintype "passive"))
    )
    (net (code "25") (name "/V_CUR") (class "Default")
      (node (ref "U4") (pin "18") (pinfunction "P0_1_18") (pintype "passive"))
      (node (ref "U5") (pin "5") (pinfunction "OUT_5") (pintype "passive"))
    )
    (net (code "26") (name "5VCC") (class "Default")
      (node (ref "C14") (pin "1") (pinfunction "1_1") (pintype "passive"))
      (node (ref "C15") (pin "1") (pinfunction "1_1") (pintype "passive"))
      (node (ref "C18") (pin "1") (pinfunction "1_1") (pintype "passive"))
      (node (ref "R9") (pin "2") (pinfunction "2_2") (pintype "passive"))
      (node (ref "U3") (pin "2") (pinfunction "VOUT_2") (pintype "passive"))
      (node (ref "U3") (pin "3") (pinfunction "FB_3") (pintype "passive"))
      (node (ref "U5") (pin "1") (pinfunction "+IN_1") (pintype "passive"))
      (node (ref "U6") (pin "9") (pinfunction "COM_9") (pintype "passive"))
    )
    (net (code "27") (name "BAT_VCC") (class "Default")
      (node (ref "C1") (pin "1") (pinfunction "1_1") (pintype "passive"))
      (node (ref "C16") (pin "1") (pinfunction "1_1") (pintype "passive"))
      (node (ref "L3") (pin "1") (pinfunction "1_1") (pintype "passive"))
      (node (ref "Q1") (pin "2") (pinfunction "S_2") (pintype "passive"))
      (node (ref "R1") (pin "1") (pinfunction "1_1") (pintype "passive"))
      (node (ref "R19") (pin "2") (pinfunction "2_2") (pintype "passive"))
      (node (ref "U1") (pin "3") (pinfunction "VIN_3") (pintype "passive"))
      (node (ref "U3") (pin "6") (pinfunction "VIN_6") (pintype "passive"))
    )
    (net (code "28") (name "CC_VCC") (class "Default")
      (node (ref "C10") (pin "1") (pinfunction "1_1") (pintype "passive"))
      (node (ref "C11") (pin "1") (pinfunction "1_1") (pintype "passive"))
      (node (ref "C3") (pin "1") (pinfunction "1_1") (pintype "passive"))
      (node (ref "C4") (pin "1") (pinfunction "1_1") (pintype "passive"))
      (node (ref "C5") (pin "1") (pinfunction "1_1") (pintype "passive"))
      (node (ref "C6") (pin "1") (pinfunction "1_1") (pintype "passive"))
      (node (ref "C7") (pin "1") (pinfunction "1_1") (pintype "passive"))
      (node (ref "C8") (pin "1") (pinfunction "1_1") (pintype "passive"))
      (node (ref "C9") (pin "1") (pinfunction "1_1") (pintype "passive"))
      (node (ref "L2") (pin "2") (pinfunction "2_2") (pintype "passive"))
      (node (ref "U4") (pin "10") (pinfunction "DVDD2_10") (pintype "passive"))
      (node (ref "U4") (pin "21") (pinfunction "AVDD5_21") (pintype "passive"))
      (node (ref "U4") (pin "24") (pinfunction "AVDD3_24") (pintype "passive"))
      (node (ref "U4") (pin "27") (pinfunction "AVDD2_27") (pintype "passive"))
      (node (ref "U4") (pin "28") (pinfunction "AVDD1_28") (pintype "passive"))
      (node (ref "U4") (pin "29") (pinfunction "AVDD4_29") (pintype "passive"))
      (node (ref "U4") (pin "31") (pinfunction "AVDD6_31") (pintype "passive"))
      (node (ref "U4") (pin "39") (pinfunction "DVDD1_39") (pintype "passive"))
    )
    (net (code "29") (name "GND") (class "Default")
      (node (ref "A1") (pin "2") (pinfunction "2_2") (pintype "passive"))
      (node (ref "B1") (pin "2") (pinfunction "2_2") (pintype "passive"))
      (node (ref "B1") (pin "5") (pinfunction "5_5") (pintype "passive"))
      (node (ref "B1") (pin "6") (pinfunction "6_6") (pintype "passive"))
      (node (ref "C1") (pin "2") (pinfunction "2_2") (pintype "passive"))
      (node (ref "C10") (pin "2") (pinfunction "2_2") (pintype "passive"))
      (node (ref "C11") (pin "2") (pinfunction "2_2") (pintype "passive"))
      (node (ref "C12") (pin "2") (pinfunction "2_2") (pintype "passive"))
      (node (ref "C13") (pin "2") (pinfunction "2_2") (pintype "passive"))
      (node (ref "C14") (pin "2") (pinfunction "2_2") (pintype "passive"))
      (node (ref "C15") (pin "2") (pinfunction "2_2") (pintype "passive"))
      (node (ref "C16") (pin "2") (pinfunction "2_2") (pintype "passive"))
      (node (ref "C17") (pin "2") (pinfunction "2_2") (pintype "passive"))
      (node (ref "C18") (pin "2") (pinfunction "2_2") (pintype "passive"))
      (node (ref "C19") (pin "1") (pinfunction "1_1") (pintype "passive"))
      (node (ref "C2") (pin "2") (pinfunction "2_2") (pintype "passive"))
      (node (ref "C20") (pin "1") (pinfunction "1_1") (pintype "passive"))
      (node (ref "C21") (pin "2") (pinfunction "2_2") (pintype "passive"))
      (node (ref "C22") (pin "2") (pinfunction "2_2") (pintype "passive"))
      (node (ref "C23") (pin "1") (pinfunction "1_1") (pintype "passive"))
      (node (ref "C24") (pin "1") (pinfunction "1_1") (pintype "passive"))
      (node (ref "C25") (pin "2") (pinfunction "2_2") (pintype "passive"))
      (node (ref "C26") (pin "2") (pinfunction "2_2") (pintype "passive"))
      (node (ref "C3") (pin "2") (pinfunction "2_2") (pintype "passive"))
      (node (ref "C4") (pin "2") (pinfunction "2_2") (pintype "passive"))
      (node (ref "C5") (pin "2") (pinfunction "2_2") (pintype "passive"))
      (node (ref "C6") (pin "2") (pinfunction "2_2") (pintype "passive"))
      (node (ref "C7") (pin "2") (pinfunction "2_2") (pintype "passive"))
      (node (ref "C8") (pin "2") (pinfunction "2_2") (pintype "passive"))
      (node (ref "C9") (pin "2") (pinfunction "2_2") (pintype "passive"))
      (node (ref "P6") (pin "1") (pinfunction "1_1") (pintype "passive"))
      (node (ref "P7") (pin "4") (pinfunction "4_4") (pintype "passive"))
      (node (ref "R12") (pin "2") (pinfunction "2_2") (pintype "passive"))
      (node (ref "R13") (pin "2") (pinfunction "2_2") (pintype "passive"))
      (node (ref "R14") (pin "2") (pinfunction "2_2") (pintype "passive"))
      (node (ref "R15") (pin "2") (pinfunction "2_2") (pintype "passive"))
      (node (ref "R16") (pin "2") (pinfunction "2_2") (pintype "passive"))
      (node (ref "R3") (pin "2") (pinfunction "2_2") (pintype "passive"))
      (node (ref "R4") (pin "2") (pinfunction "2_2") (pintype "passive"))
      (node (ref "R5") (pin "2") (pinfunction "2_2") (pintype "passive"))
      (node (ref "R7") (pin "2") (pinfunction "2_2") (pintype "passive"))
      (node (ref "RT1") (pin "2") (pinfunction "2_2") (pintype "passive"))
      (node (ref "S1") (pin "2") (pinfunction "2_2") (pintype "passive"))
      (node (ref "U1") (pin "4") (pinfunction "GND_4") (pintype "passive"))
      (node (ref "U2") (pin "5") (pinfunction "GND_5") (pintype "passive"))
      (node (ref "U3") (pin "1") (pinfunction "GND_1") (pintype "passive"))
      (node (ref "U3") (pin "7") (pinfunction "_GND_7") (pintype "passive"))
      (node (ref "U4") (pin "1") (pinfunction "GND_1") (pintype "passive"))
      (node (ref "U4") (pin "2") (pinfunction "GND_2") (pintype "passive"))
      (node (ref "U4") (pin "3") (pinfunction "GND_3") (pintype "passive"))
      (node (ref "U4") (pin "4") (pinfunction "GND_4") (pintype "passive"))
      (node (ref "U5") (pin "4") (pinfunction "GND_4") (pintype "passive"))
      (node (ref "U6") (pin "8") (pinfunction "E_8") (pintype "passive"))
      (node (ref "U7") (pin "1") (pinfunction "DU_1") (pintype "passive"))
      (node (ref "U7") (pin "2") (pinfunction "DU_2") (pintype "passive"))
      (node (ref "U7") (pin "4") (pinfunction "Vss_4") (pintype "passive"))
    )
    (net (code "30") (name "Net-(A1-Pad1)") (class "Default")
      (node (ref "A1") (pin "1") (pinfunction "1_1") (pintype "passive"))
      (node (ref "R8") (pin "2") (pinfunction "2_2") (pintype "passive"))
    )
    (net (code "31") (name "Net-(B1-Pad1)") (class "Default")
      (node (ref "B1") (pin "1") (pinfunction "1_1") (pintype "passive"))
      (node (ref "C17") (pin "1") (pinfunction "1_1") (pintype "passive"))
      (node (ref "R8") (pin "1") (pinfunction "1_1") (pintype "passive"))
    )
    (net (code "32") (name "Net-(D3-K)") (class "Default")
      (node (ref "D3") (pin "2") (pinfunction "K_2") (pintype "passive"))
      (node (ref "D4") (pin "2") (pinfunction "K_2") (pintype "passive"))
      (node (ref "P8") (pin "4") (pinfunction "4_4") (pintype "passive"))
      (node (ref "S2") (pin "2") (pinfunction "2_2") (pintype "passive"))
    )
    (net (code "33") (name "Net-(L4-Pad1)") (class "Default")
      (node (ref "L4") (pin "1") (pinfunction "1_1") (pintype "passive"))
      (node (ref "R16") (pin "1") (pinfunction "1_1") (pintype "passive"))
    )
    (net (code "34") (name "Net-(P6-Pad5)") (class "Default")
      (node (ref "P6") (pin "5") (pinfunction "5_5") (pintype "passive"))
      (node (ref "R18") (pin "1") (pinfunction "1_1") (pintype "passive"))
    )
    (net (code "35") (name "Net-(P6-Pad9)") (class "Default")
      (node (ref "P6") (pin "9") (pinfunction "9_9") (pintype "passive"))
      (node (ref "R19") (pin "1") (pinfunction "1_1") (pintype "passive"))
    )
    (net (code "36") (name "Net-(P7-Pad2)") (class "Default")
      (node (ref "P7") (pin "2") (pinfunction "2_2") (pintype "passive"))
      (node (ref "R21") (pin "1") (pinfunction "1_1") (pintype "passive"))
    )
    (net (code "37") (name "Net-(P7-Pad3)") (class "Default")
      (node (ref "P7") (pin "3") (pinfunction "3_3") (pintype "passive"))
      (node (ref "R22") (pin "1") (pinfunction "1_1") (pintype "passive"))
    )
    (net (code "38") (name "Net-(Q1-D)") (class "Default")
      (node (ref "F1") (pin "2") (pinfunction "2_2") (pintype "passive"))
      (node (ref "Q1") (pin "3") (pinfunction "D_3") (pintype "passive"))
      (node (ref "R1") (pin "2") (pinfunction "2_2") (pintype "passive"))
    )
    (net (code "39") (name "Net-(Q1-G)") (class "Default")
      (node (ref "Q1") (pin "1") (pinfunction "G_1") (pintype "passive"))
      (node (ref "R3") (pin "1") (pinfunction "1_1") (pintype "passive"))
    )
    (net (code "40") (name "Net-(R17-Pad1)") (class "Default")
      (node (ref "R17") (pin "1") (pinfunction "1_1") (pintype "passive"))
      (node (ref "S1") (pin "1") (pinfunction "1_1") (pintype "passive"))
    )
    (net (code "41") (name "Net-(U1-SW)") (class "Default")
      (node (ref "L1") (pin "1") (pinfunction "1_1") (pintype "passive"))
      (node (ref "U1") (pin "2") (pinfunction "SW_2") (pintype "passive"))
    )
    (net (code "42") (name "Net-(U2-CG)") (class "Default")
      (node (ref "P2") (pin "1") (pinfunction "1_1") (pintype "passive"))
      (node (ref "P3") (pin "1") (pinfunction "1_1") (pintype "passive"))
      (node (ref "P4") (pin "1") (pinfunction "1_1") (pintype "passive"))
      (node (ref "R4") (pin "1") (pinfunction "1_1") (pintype "passive"))
      (node (ref "U2") (pin "6") (pinfunction "CG_6") (pintype "passive"))
    )
    (net (code "43") (name "Net-(U2-ROSC)") (class "Default")
      (node (ref "R5") (pin "1") (pinfunction "1_1") (pintype "passive"))
      (node (ref "U2") (pin "2") (pinfunction "ROSC_2") (pintype "passive"))
    )
    (net (code "44") (name "Net-(U2-VCC)") (class "Default")
      (node (ref "C12") (pin "1") (pinfunction "1_1") (pintype "passive"))
      (node (ref "F1") (pin "1") (pinfunction "1_1") (pintype "passive"))
      (node (ref "P1") (pin "1") (pinfunction "1_1") (pintype "passive"))
      (node (ref "R6") (pin "1") (pinfunction "1_1") (pintype "passive"))
      (node (ref "U2") (pin "7") (pinfunction "VCC_7") (pintype "passive"))
    )
    (net (code "45") (name "Net-(U2-VIN)") (class "Default")
      (node (ref "C13") (pin "1") (pinfunction "1_1") (pintype "passive"))
      (node (ref "R6") (pin "2") (pinfunction "2_2") (pintype "passive"))
      (node (ref "U2") (pin "8") (pinfunction "VIN_8") (pintype "passive"))
    )
    (net (code "46") (name "Net-(U3-L)") (class "Default")
      (node (ref "L3") (pin "2") (pinfunction "2_2") (pintype "passive"))
      (node (ref "U3") (pin "5") (pinfunction "L_5") (pintype "passive"))
    )
    (net (code "47") (name "Net-(U4-DCOUPL)") (class "Default")
      (node (ref "C21") (pin "1") (pinfunction "1_1") (pintype "passive"))
      (node (ref "U4") (pin "40") (pinfunction "DCOUPL_40") (pintype "passive"))
    )
    (net (code "48") (name "Net-(U4-P2_3{slash}XOSC32K_Q2)") (class "Default")
      (node (ref "BQ1") (pin "2") (pintype "passive"))
      (node (ref "C20") (pin "2") (pinfunction "2_2") (pintype "passive"))
      (node (ref "U4") (pin "33") (pinfunction "P2_3/XOSC32K_Q2_33") (pintype "passive"))
    )
    (net (code "49") (name "Net-(U4-P2_4{slash}XOSC32K_Q1)") (class "Default")
      (node (ref "BQ1") (pin "1") (pintype "passive"))
      (node (ref "C19") (pin "2") (pinfunction "2_2") (pintype "passive"))
      (node (ref "U4") (pin "32") (pinfunction "P2_4/XOSC32K_Q1_32") (pintype "passive"))
    )
    (net (code "50") (name "Net-(U4-RBIAS)") (class "Default")
      (node (ref "L4") (pin "2") (pinfunction "2_2") (pintype "passive"))
      (node (ref "U4") (pin "30") (pinfunction "RBIAS_30") (pintype "passive"))
    )
    (net (code "51") (name "Net-(U4-RF_N)") (class "Default")
      (node (ref "B1") (pin "3") (pinfunction "3_3") (pintype "passive"))
      (node (ref "U4") (pin "26") (pinfunction "RF_N_26") (pintype "passive"))
    )
    (net (code "52") (name "Net-(U4-RF_P)") (class "Default")
      (node (ref "B1") (pin "4") (pinfunction "4_4") (pintype "passive"))
      (node (ref "U4") (pin "25") (pinfunction "RF_P_25") (pintype "passive"))
    )
    (net (code "53") (name "Net-(U4-XOSC_Q1)") (class "Default")
      (node (ref "BQ2") (pin "1") (pintype "passive"))
      (node (ref "C23") (pin "2") (pinfunction "2_2") (pintype "passive"))
      (node (ref "U4") (pin "22") (pinfunction "XOSC_Q1_22") (pintype "passive"))
    )
    (net (code "54") (name "Net-(U4-XOSC_Q2)") (class "Default")
      (node (ref "BQ2") (pin "3") (pintype "passive"))
      (node (ref "C24") (pin "2") (pinfunction "2_2") (pintype "passive"))
      (node (ref "U4") (pin "23") (pinfunction "XOSC_Q2_23") (pintype "passive"))
    )
    (net (code "55") (name "Net-(U5-IN)") (class "Default")
      (node (ref "P5") (pin "1") (pinfunction "1_1") (pintype "passive"))
      (node (ref "R9") (pin "1") (pinfunction "1_1") (pintype "passive"))
      (node (ref "U5") (pin "8") (pinfunction "IN_8") (pintype "passive"))
    )
    (net (code "56") (name "VCC") (class "Default")
      (node (ref "C2") (pin "1") (pinfunction "1_1") (pintype "passive"))
      (node (ref "L1") (pin "2") (pinfunction "2_2") (pintype "passive"))
      (node (ref "L2") (pin "1") (pinfunction "1_1") (pintype "passive"))
      (node (ref "P6") (pin "2") (pinfunction "2_2") (pintype "passive"))
      (node (ref "R10") (pin "2") (pinfunction "2_2") (pintype "passive"))
      (node (ref "R11") (pin "2") (pinfunction "2_2") (pintype "passive"))
      (node (ref "R2") (pin "1") (pinfunction "1_1") (pintype "passive"))
      (node (ref "R20") (pin "1") (pinfunction "1_1") (pintype "passive"))
      (node (ref "U1") (pin "6") (pinfunction "VOUT_6") (pintype "passive"))
      (node (ref "U7") (pin "8") (pinfunction "Vcc_8") (pintype "passive"))
    )
    (net (code "57") (name "unconnected-(U2-IO0-Pad1)") (class "Default")
      (node (ref "U2") (pin "1") (pinfunction "IO0_1") (pintype "passive+no_connect"))
    )
    (net (code "58") (name "unconnected-(U4-P1_4-Pad6)") (class "Default")
      (node (ref "U4") (pin "6") (pinfunction "P1_4_6") (pintype "passive+no_connect"))
    )
    (net (code "59") (name "unconnected-(U4-P1_6-Pad38)") (class "Default")
      (node (ref "U4") (pin "38") (pinfunction "P1_6_38") (pintype "passive+no_connect"))
    )
    (net (code "60") (name "unconnected-(U5-NC-Pad2)") (class "Default")
      (node (ref "U5") (pin "2") (pinfunction "NC_2") (pintype "passive+no_connect"))
    )
    (net (code "61") (name "unconnected-(U5-NC-Pad3)") (class "Default")
      (node (ref "U5") (pin "3") (pinfunction "NC_3") (pintype "passive+no_connect"))
    )
    (net (code "62") (name "unconnected-(U5-NC-Pad6)") (class "Default")
      (node (ref "U5") (pin "6") (pinfunction "NC_6") (pintype "passive+no_connect"))
    )
    (net (code "63") (name "unconnected-(U5-NC-Pad7)") (class "Default")
      (node (ref "U5") (pin "7") (pinfunction "NC_7") (pintype "passive+no_connect"))
    )
    (net (code "64") (name "unconnected-(U6-1B-Pad1)") (class "Default")
      (node (ref "U6") (pin "1") (pinfunction "1B_1") (pintype "passive"))
    )
    (net (code "65") (name "unconnected-(U6-1C-Pad16)") (class "Default")
      (node (ref "U6") (pin "16") (pinfunction "1C_16") (pintype "passive"))
    )
    (net (code "66") (name "unconnected-(U6-2B-Pad2)") (class "Default")
      (node (ref "U6") (pin "2") (pinfunction "2B_2") (pintype "passive"))
    )
    (net (code "67") (name "unconnected-(U6-2C-Pad15)") (class "Default")
      (node (ref "U6") (pin "15") (pinfunction "2C_15") (pintype "passive"))
    )
    (net (code "68") (name "unconnected-(U6-3B-Pad3)") (class "Default")
      (node (ref "U6") (pin "3") (pinfunction "3B_3") (pintype "passive"))
    )
    (net (code "69") (name "unconnected-(U6-3C-Pad14)") (class "Default")
      (node (ref "U6") (pin "14") (pinfunction "3C_14") (pintype "passive"))
    )
    (net (code "70") (name "unconnected-(U7-E2-Pad3)") (class "Default")
      (node (ref "U7") (pin "3") (pinfunction "E2_3") (pintype "passive"))
    )
    (net (code "71") (name "unconnected-(U7-{slash}WC-Pad7)") (class "Default")
      (node (ref "U7") (pin "7") (pinfunction "/WC_7") (pintype "passive"))
    )
  )
)
